# Input.net
KiCad netlist of a schematic drawn in Altium Designer
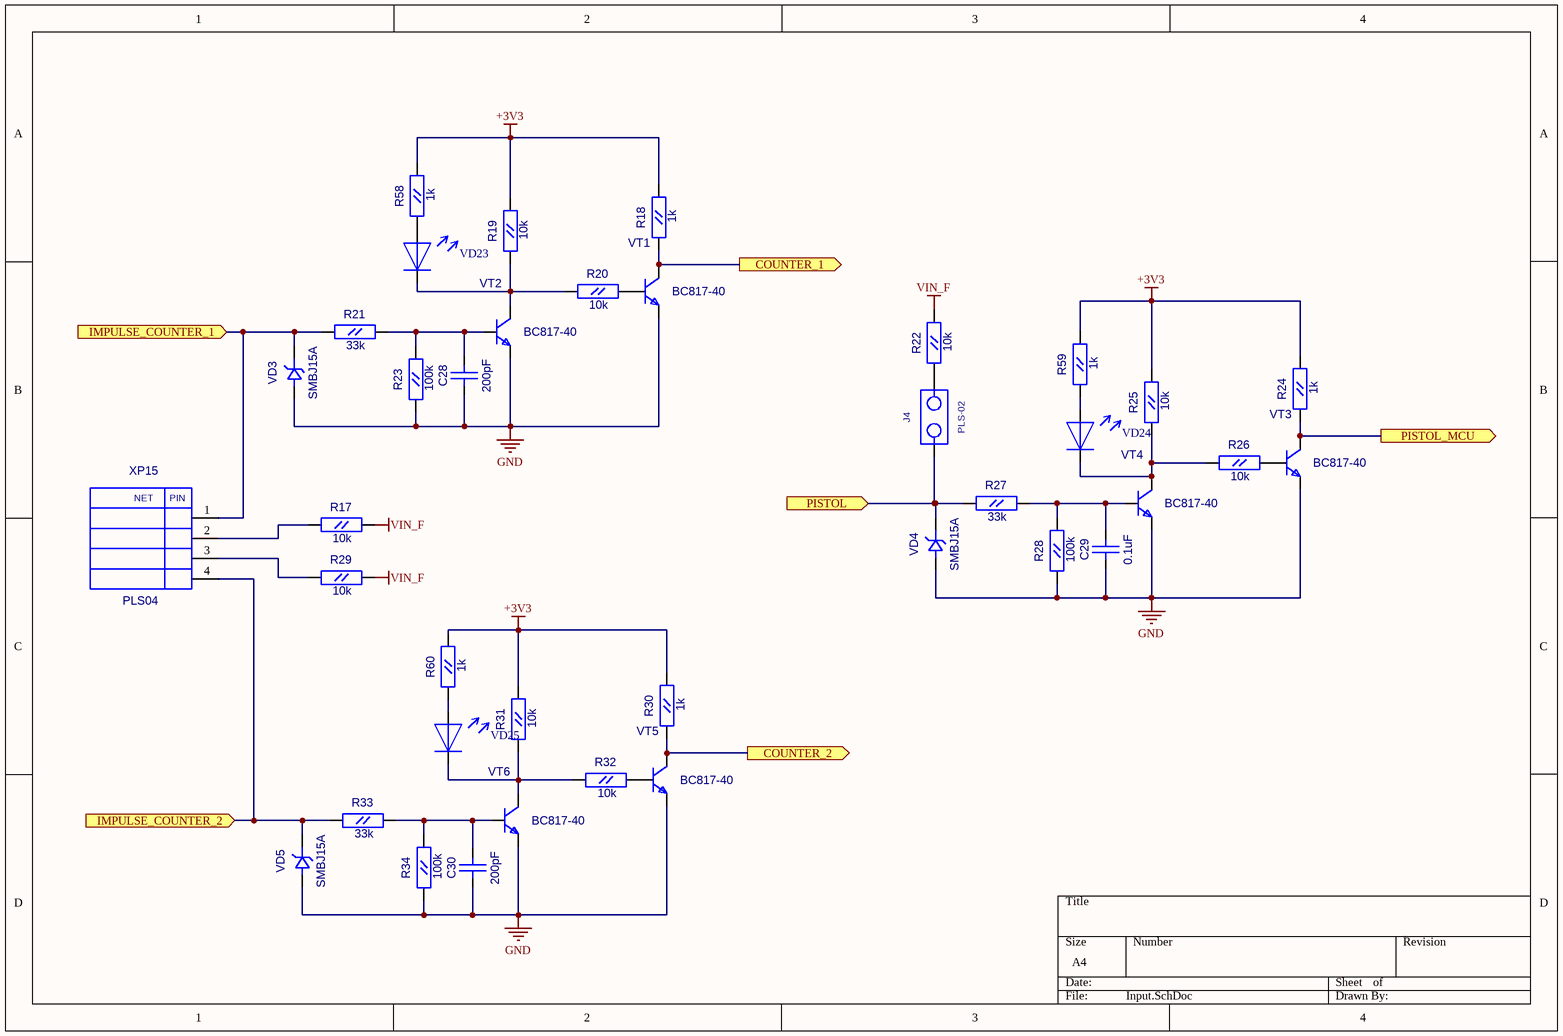
[diagram p0: Input.SchDoc]

(export (version "E")
  (design (tool "Eeschema 10.0.6"))
  (components
    (comp (ref "C28")
      (value "200pF")
      (footprint "CC0603")
      (description "CC0603")
      (libsource (lib "gprs_modem_2") (part "CC0603"))
    )
    (comp (ref "C29")
      (value "0.1uF")
      (footprint "CC0603")
      (description "CC0603")
      (libsource (lib "gprs_modem_2") (part "CC0603"))
    )
    (comp (ref "C30")
      (value "200pF")
      (footprint "CC0603")
      (description "CC0603")
      (libsource (lib "gprs_modem_2") (part "CC0603"))
    )
    (comp (ref "J4") (value "PLS-02") (footprint "PLS-02") (libsource (lib "gprs_modem_2") (part "PLS-02")))
    (comp (ref "R17")
      (value "10k")
      (footprint "RC0603")
      (description "RC0603")
      (libsource (lib "gprs_modem_2") (part "RC0603"))
    )
    (comp (ref "R18")
      (value "1k")
      (footprint "RC0603")
      (description "RC0603")
      (libsource (lib "gprs_modem_2") (part "RC0603"))
    )
    (comp (ref "R19")
      (value "10k")
      (footprint "RC0603")
      (description "RC0603")
      (libsource (lib "gprs_modem_2") (part "RC0603"))
    )
    (comp (ref "R20")
      (value "10k")
      (footprint "RC0603")
      (description "RC0603")
      (libsource (lib "gprs_modem_2") (part "RC0603"))
    )
    (comp (ref "R21")
      (value "33k")
      (footprint "RC0603")
      (description "RC0603")
      (libsource (lib "gprs_modem_2") (part "RC0603"))
    )
    (comp (ref "R22")
      (value "10k")
      (footprint "RC0603")
      (description "RC0603")
      (libsource (lib "gprs_modem_2") (part "RC0603"))
    )
    (comp (ref "R23")
      (value "100k")
      (footprint "RC0603")
      (description "RC0603")
      (libsource (lib "gprs_modem_2") (part "RC0603"))
    )
    (comp (ref "R24")
      (value "1k")
      (footprint "RC0603")
      (description "RC0603")
      (libsource (lib "gprs_modem_2") (part "RC0603"))
    )
    (comp (ref "R25")
      (value "10k")
      (footprint "RC0603")
      (description "RC0603")
      (libsource (lib "gprs_modem_2") (part "RC0603"))
    )
    (comp (ref "R26")
      (value "10k")
      (footprint "RC0603")
      (description "RC0603")
      (libsource (lib "gprs_modem_2") (part "RC0603"))
    )
    (comp (ref "R27")
      (value "33k")
      (footprint "RC0603")
      (description "RC0603")
      (libsource (lib "gprs_modem_2") (part "RC0603"))
    )
    (comp (ref "R28")
      (value "100k")
      (footprint "RC0603")
      (description "RC0603")
      (libsource (lib "gprs_modem_2") (part "RC0603"))
    )
    (comp (ref "R29")
      (value "10k")
      (footprint "RC0603")
      (description "RC0603")
      (libsource (lib "gprs_modem_2") (part "RC0603"))
    )
    (comp (ref "R30")
      (value "1k")
      (footprint "RC0603")
      (description "RC0603")
      (libsource (lib "gprs_modem_2") (part "RC0603"))
    )
    (comp (ref "R31")
      (value "10k")
      (footprint "RC0603")
      (description "RC0603")
      (libsource (lib "gprs_modem_2") (part "RC0603"))
    )
    (comp (ref "R32")
      (value "10k")
      (footprint "RC0603")
      (description "RC0603")
      (libsource (lib "gprs_modem_2") (part "RC0603"))
    )
    (comp (ref "R33")
      (value "33k")
      (footprint "RC0603")
      (description "RC0603")
      (libsource (lib "gprs_modem_2") (part "RC0603"))
    )
    (comp (ref "R34")
      (value "100k")
      (footprint "RC0603")
      (description "RC0603")
      (libsource (lib "gprs_modem_2") (part "RC0603"))
    )
    (comp (ref "R58")
      (value "1k")
      (footprint "RC0603")
      (description "RC0603")
      (libsource (lib "gprs_modem_2") (part "RC0603"))
    )
    (comp (ref "R59")
      (value "1k")
      (footprint "RC0603")
      (description "RC0603")
      (libsource (lib "gprs_modem_2") (part "RC0603"))
    )
    (comp (ref "R60")
      (value "1k")
      (footprint "RC0603")
      (description "RC0603")
      (libsource (lib "gprs_modem_2") (part "RC0603"))
    )
    (comp (ref "VD3")
      (value "SMBJ15A")
      (footprint "SMB")
      (description "SMBJ")
      (libsource (lib "gprs_modem_2") (part "SMBJ"))
    )
    (comp (ref "VD4")
      (value "SMBJ15A")
      (footprint "SMB")
      (description "SMBJ")
      (libsource (lib "gprs_modem_2") (part "SMBJ"))
    )
    (comp (ref "VD5")
      (value "SMBJ15A")
      (footprint "SMB")
      (description "SMBJ")
      (libsource (lib "gprs_modem_2") (part "SMBJ"))
    )
    (comp (ref "VD23")
      (value "LED_0805")
      (footprint "LED0805")
      (libsource (lib "gprs_modem_2") (part "LED_0805"))
    )
    (comp (ref "VD24")
      (value "LED_0805")
      (footprint "LED0805")
      (libsource (lib "gprs_modem_2") (part "LED_0805"))
    )
    (comp (ref "VD25")
      (value "LED_0805")
      (footprint "LED0805")
      (libsource (lib "gprs_modem_2") (part "LED_0805"))
    )
    (comp (ref "VT1")
      (value "BC817-40")
      (footprint "SOT-23(123)")
      (description "NPN 500ma transistor")
      (libsource (lib "gprs_modem_2") (part "BC846BLT1"))
    )
    (comp (ref "VT2")
      (value "BC817-40")
      (footprint "SOT-23(123)")
      (description "NPN 500ma transistor")
      (libsource (lib "gprs_modem_2") (part "BC846BLT1"))
    )
    (comp (ref "VT3")
      (value "BC817-40")
      (footprint "SOT-23(123)")
      (description "NPN 500ma transistor")
      (libsource (lib "gprs_modem_2") (part "BC846BLT1"))
    )
    (comp (ref "VT4")
      (value "BC817-40")
      (footprint "SOT-23(123)")
      (description "NPN 500ma transistor")
      (libsource (lib "gprs_modem_2") (part "BC846BLT1"))
    )
    (comp (ref "VT5")
      (value "BC817-40")
      (footprint "SOT-23(123)")
      (description "NPN 500ma transistor")
      (libsource (lib "gprs_modem_2") (part "BC846BLT1"))
    )
    (comp (ref "VT6")
      (value "BC817-40")
      (footprint "SOT-23(123)")
      (description "NPN 500ma transistor")
      (libsource (lib "gprs_modem_2") (part "BC846BLT1"))
    )
    (comp (ref "XP15") (value "PLS04") (footprint "PIN04S") (libsource (lib "gprs_modem_2") (part "PLS04")))
  )
  (nets
    (net (code "1") (name "+3V3") (class "Default")
      (node (ref "R18") (pin "2") (pinfunction "B_2") (pintype "passive"))
      (node (ref "R19") (pin "2") (pinfunction "B_2") (pintype "passive"))
      (node (ref "R24") (pin "2") (pinfunction "B_2") (pintype "passive"))
      (node (ref "R25") (pin "2") (pinfunction "B_2") (pintype "passive"))
      (node (ref "R30") (pin "2") (pinfunction "B_2") (pintype "passive"))
      (node (ref "R31") (pin "2") (pinfunction "B_2") (pintype "passive"))
      (node (ref "R58") (pin "2") (pinfunction "B_2") (pintype "passive"))
      (node (ref "R59") (pin "2") (pinfunction "B_2") (pintype "passive"))
      (node (ref "R60") (pin "2") (pinfunction "B_2") (pintype "passive"))
    )
    (net (code "2") (name "/COUNTER_1") (class "Default")
      (node (ref "R18") (pin "1") (pinfunction "A_1") (pintype "passive"))
      (node (ref "VT1") (pin "3") (pinfunction "C_3") (pintype "passive"))
    )
    (net (code "3") (name "/COUNTER_2") (class "Default")
      (node (ref "R30") (pin "1") (pinfunction "A_1") (pintype "passive"))
      (node (ref "VT5") (pin "3") (pinfunction "C_3") (pintype "passive"))
    )
    (net (code "4") (name "/IMPULSE_COUNTER_1") (class "Default")
      (node (ref "R21") (pin "1") (pinfunction "A_1") (pintype "passive"))
      (node (ref "VD3") (pin "2") (pinfunction "K_2") (pintype "passive"))
      (node (ref "XP15") (pin "1") (pinfunction "1_1") (pintype "passive"))
    )
    (net (code "5") (name "/IMPULSE_COUNTER_2") (class "Default")
      (node (ref "R33") (pin "1") (pinfunction "A_1") (pintype "passive"))
      (node (ref "VD5") (pin "2") (pinfunction "K_2") (pintype "passive"))
      (node (ref "XP15") (pin "4") (pinfunction "4_4") (pintype "passive"))
    )
    (net (code "6") (name "/PISTOL") (class "Default")
      (node (ref "J4") (pin "1") (pintype "passive"))
      (node (ref "R27") (pin "1") (pinfunction "A_1") (pintype "passive"))
      (node (ref "VD4") (pin "2") (pinfunction "K_2") (pintype "passive"))
    )
    (net (code "7") (name "/PISTOL_MCU") (class "Default")
      (node (ref "R24") (pin "1") (pinfunction "A_1") (pintype "passive"))
      (node (ref "VT3") (pin "3") (pinfunction "C_3") (pintype "passive"))
    )
    (net (code "8") (name "GND") (class "Default")
      (node (ref "C28") (pin "1") (pinfunction "A_1") (pintype "passive"))
      (node (ref "C29") (pin "1") (pinfunction "A_1") (pintype "passive"))
      (node (ref "C30") (pin "1") (pinfunction "A_1") (pintype "passive"))
      (node (ref "R23") (pin "1") (pinfunction "A_1") (pintype "passive"))
      (node (ref "R28") (pin "1") (pinfunction "A_1") (pintype "passive"))
      (node (ref "R34") (pin "1") (pinfunction "A_1") (pintype "passive"))
      (node (ref "VD3") (pin "1") (pinfunction "A_1") (pintype "passive"))
      (node (ref "VD4") (pin "1") (pinfunction "A_1") (pintype "passive"))
      (node (ref "VD5") (pin "1") (pinfunction "A_1") (pintype "passive"))
      (node (ref "VT1") (pin "2") (pinfunction "E_2") (pintype "passive"))
      (node (ref "VT2") (pin "2") (pinfunction "E_2") (pintype "passive"))
      (node (ref "VT3") (pin "2") (pinfunction "E_2") (pintype "passive"))
      (node (ref "VT4") (pin "2") (pinfunction "E_2") (pintype "passive"))
      (node (ref "VT5") (pin "2") (pinfunction "E_2") (pintype "passive"))
      (node (ref "VT6") (pin "2") (pinfunction "E_2") (pintype "passive"))
    )
    (net (code "9") (name "Net-(C28-B)") (class "Default")
      (node (ref "C28") (pin "2") (pinfunction "B_2") (pintype "passive"))
      (node (ref "R21") (pin "2") (pinfunction "B_2") (pintype "passive"))
      (node (ref "R23") (pin "2") (pinfunction "B_2") (pintype "passive"))
      (node (ref "VT2") (pin "1") (pinfunction "B_1") (pintype "passive"))
    )
    (net (code "10") (name "Net-(C29-B)") (class "Default")
      (node (ref "C29") (pin "2") (pinfunction "B_2") (pintype "passive"))
      (node (ref "R27") (pin "2") (pinfunction "B_2") (pintype "passive"))
      (node (ref "R28") (pin "2") (pinfunction "B_2") (pintype "passive"))
      (node (ref "VT4") (pin "1") (pinfunction "B_1") (pintype "passive"))
    )
    (net (code "11") (name "Net-(C30-B)") (class "Default")
      (node (ref "C30") (pin "2") (pinfunction "B_2") (pintype "passive"))
      (node (ref "R33") (pin "2") (pinfunction "B_2") (pintype "passive"))
      (node (ref "R34") (pin "2") (pinfunction "B_2") (pintype "passive"))
      (node (ref "VT6") (pin "1") (pinfunction "B_1") (pintype "passive"))
    )
    (net (code "12") (name "Net-(R17-A)") (class "Default")
      (node (ref "R17") (pin "1") (pinfunction "A_1") (pintype "passive"))
      (node (ref "XP15") (pin "2") (pinfunction "2_2") (pintype "passive"))
    )
    (net (code "13") (name "Net-(R19-A)") (class "Default")
      (node (ref "R19") (pin "1") (pinfunction "A_1") (pintype "passive"))
      (node (ref "R20") (pin "1") (pinfunction "A_1") (pintype "passive"))
      (node (ref "VD23") (pin "2") (pintype "passive"))
      (node (ref "VT2") (pin "3") (pinfunction "C_3") (pintype "passive"))
    )
    (net (code "14") (name "Net-(R20-B)") (class "Default")
      (node (ref "R20") (pin "2") (pinfunction "B_2") (pintype "passive"))
      (node (ref "VT1") (pin "1") (pinfunction "B_1") (pintype "passive"))
    )
    (net (code "15") (name "Net-(R22-A)") (class "Default")
      (node (ref "J4") (pin "2") (pintype "passive"))
      (node (ref "R22") (pin "1") (pinfunction "A_1") (pintype "passive"))
    )
    (net (code "16") (name "Net-(R25-A)") (class "Default")
      (node (ref "R25") (pin "1") (pinfunction "A_1") (pintype "passive"))
      (node (ref "R26") (pin "1") (pinfunction "A_1") (pintype "passive"))
      (node (ref "VD24") (pin "2") (pintype "passive"))
      (node (ref "VT4") (pin "3") (pinfunction "C_3") (pintype "passive"))
    )
    (net (code "17") (name "Net-(R26-B)") (class "Default")
      (node (ref "R26") (pin "2") (pinfunction "B_2") (pintype "passive"))
      (node (ref "VT3") (pin "1") (pinfunction "B_1") (pintype "passive"))
    )
    (net (code "18") (name "Net-(R29-A)") (class "Default")
      (node (ref "R29") (pin "1") (pinfunction "A_1") (pintype "passive"))
      (node (ref "XP15") (pin "3") (pinfunction "3_3") (pintype "passive"))
    )
    (net (code "19") (name "Net-(R31-A)") (class "Default")
      (node (ref "R31") (pin "1") (pinfunction "A_1") (pintype "passive"))
      (node (ref "R32") (pin "1") (pinfunction "A_1") (pintype "passive"))
      (node (ref "VD25") (pin "2") (pintype "passive"))
      (node (ref "VT6") (pin "3") (pinfunction "C_3") (pintype "passive"))
    )
    (net (code "20") (name "Net-(R32-B)") (class "Default")
      (node (ref "R32") (pin "2") (pinfunction "B_2") (pintype "passive"))
      (node (ref "VT5") (pin "1") (pinfunction "B_1") (pintype "passive"))
    )
    (net (code "21") (name "Net-(R58-A)") (class "Default")
      (node (ref "R58") (pin "1") (pinfunction "A_1") (pintype "passive"))
      (node (ref "VD23") (pin "1") (pintype "passive"))
    )
    (net (code "22") (name "Net-(R59-A)") (class "Default")
      (node (ref "R59") (pin "1") (pinfunction "A_1") (pintype "passive"))
      (node (ref "VD24") (pin "1") (pintype "passive"))
    )
    (net (code "23") (name "Net-(R60-A)") (class "Default")
      (node (ref "R60") (pin "1") (pinfunction "A_1") (pintype "passive"))
      (node (ref "VD25") (pin "1") (pintype "passive"))
    )
    (net (code "24") (name "VIN_F") (class "Default")
      (node (ref "R17") (pin "2") (pinfunction "B_2") (pintype "passive"))
      (node (ref "R22") (pin "2") (pinfunction "B_2") (pintype "passive"))
      (node (ref "R29") (pin "2") (pinfunction "B_2") (pintype "passive"))
    )
  )
)
